# Microcontroller.net
KiCad netlist of a schematic drawn in Altium Designer
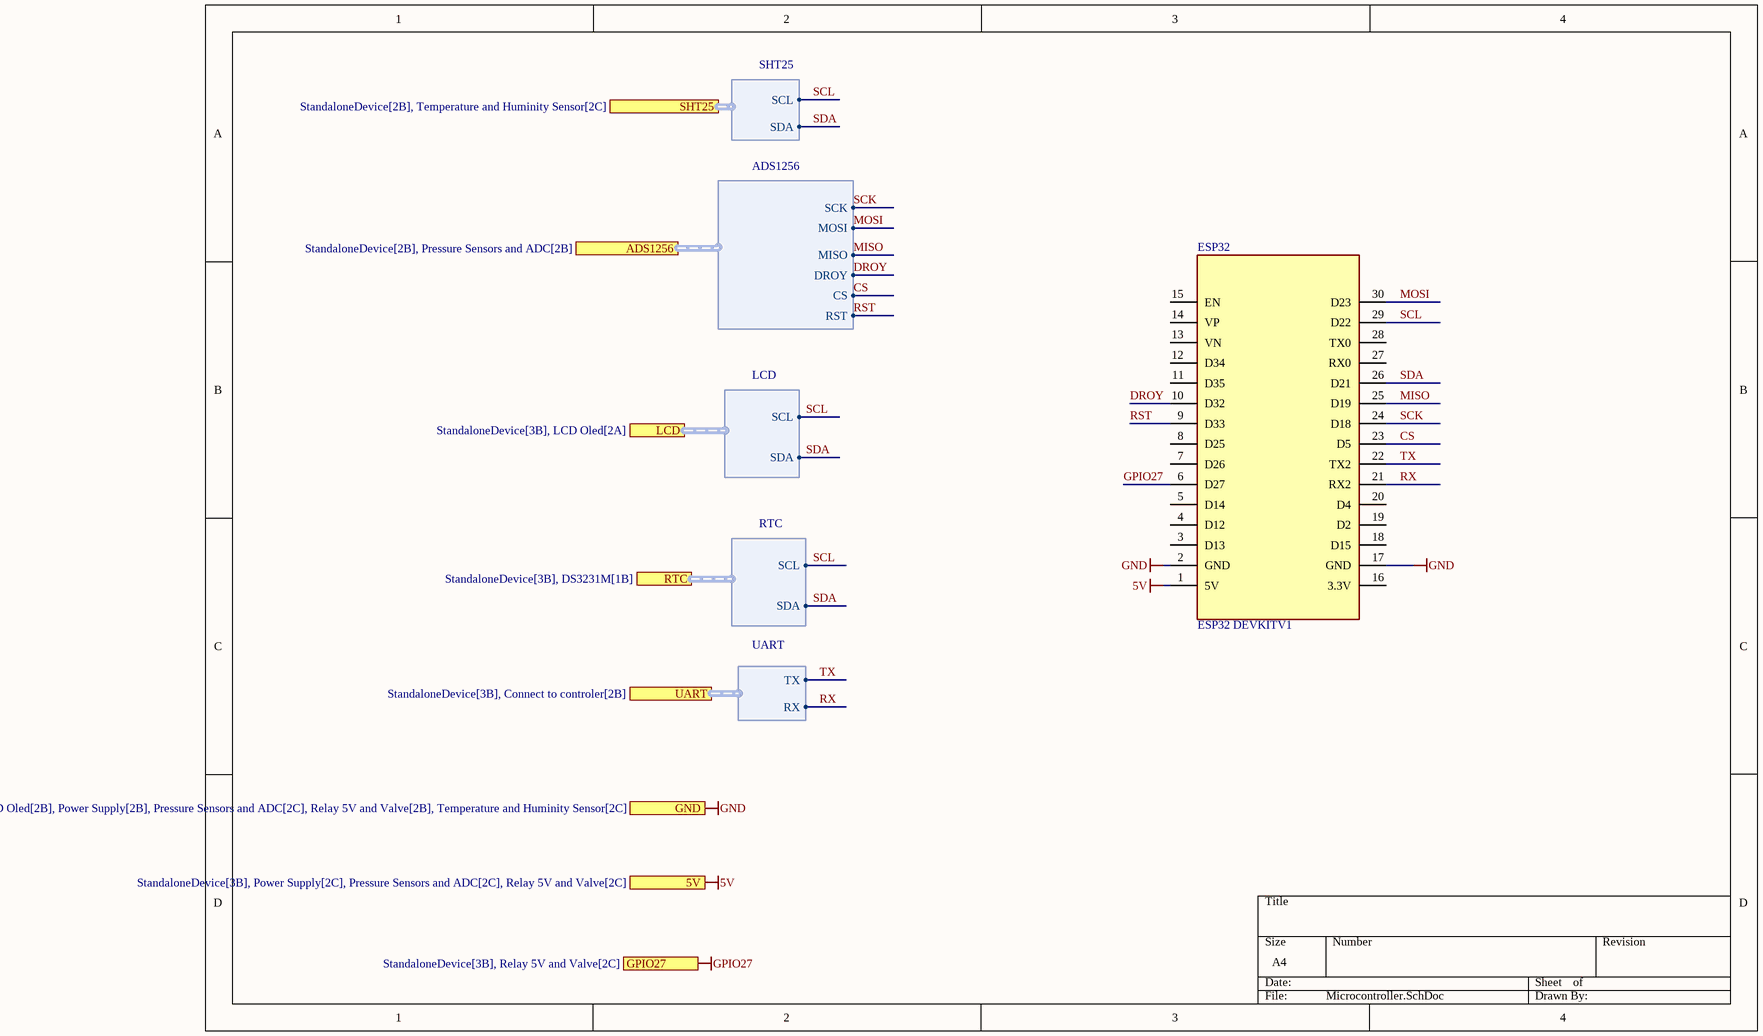
[diagram p0: Microcontroller.SchDoc]

(export (version "E")
  (design (tool "Eeschema 10.0.6"))
  (components
    (comp (ref "ESP32")
      (value "ESP32 DEVKITV1")
      (footprint "ESP32 DEVKITV1")
      (fields (field (name "MF") "Espressif Systems") (field (name "MP") "ESP32 NODEMCU"))
      (libsource (lib "KHOEMACH_SCHLIB") (part "ESP32 DEVKITV1"))
    )
  )
  (nets
    (net (code "7") (name "/CS") (class "Default")
      (node (ref "ESP32") (pin "23") (pinfunction "D5_23") (pintype "power_in"))
    )
    (net (code "8") (name "/DROY") (class "Default")
      (node (ref "ESP32") (pin "10") (pinfunction "D32_10") (pintype "power_in"))
    )
    (net (code "9") (name "/MISO") (class "Default")
      (node (ref "ESP32") (pin "25") (pinfunction "D19_25") (pintype "power_in"))
    )
    (net (code "10") (name "/MOSI") (class "Default")
      (node (ref "ESP32") (pin "30") (pinfunction "D23_30") (pintype "power_in"))
    )
    (net (code "11") (name "/RST") (class "Default")
      (node (ref "ESP32") (pin "9") (pinfunction "D33_9") (pintype "power_in"))
    )
    (net (code "12") (name "/RX") (class "Default")
      (node (ref "ESP32") (pin "21") (pinfunction "RX2_21") (pintype "power_in"))
    )
    (net (code "13") (name "/SCK") (class "Default")
      (node (ref "ESP32") (pin "24") (pinfunction "D18_24") (pintype "power_in"))
    )
    (net (code "14") (name "/SCL") (class "Default")
      (node (ref "ESP32") (pin "29") (pinfunction "D22_29") (pintype "power_in"))
    )
    (net (code "15") (name "/SDA") (class "Default")
      (node (ref "ESP32") (pin "26") (pinfunction "D21_26") (pintype "power_in"))
    )
    (net (code "16") (name "/TX") (class "Default")
      (node (ref "ESP32") (pin "22") (pinfunction "TX2_22") (pintype "power_in"))
    )
    (net (code "22") (name "5V") (class "Default")
      (node (ref "ESP32") (pin "1") (pinfunction "5V_1") (pintype "power_in"))
    )
    (net (code "23") (name "GND") (class "Default")
      (node (ref "ESP32") (pin "17") (pinfunction "GND_17") (pintype "power_in"))
      (node (ref "ESP32") (pin "2") (pinfunction "GND_2") (pintype "power_in"))
    )
    (net (code "24") (name "GPIO27") (class "Default")
      (node (ref "ESP32") (pin "6") (pinfunction "D27_6") (pintype "power_in"))
    )
    (net (code "25") (name "unconnected-(ESP32-3.3V-Pad16)") (class "Default")
      (node (ref "ESP32") (pin "16") (pinfunction "3.3V_16") (pintype "power_in"))
    )
    (net (code "26") (name "unconnected-(ESP32-D2-Pad19)") (class "Default")
      (node (ref "ESP32") (pin "19") (pinfunction "D2_19") (pintype "power_in"))
    )
    (net (code "27") (name "unconnected-(ESP32-D4-Pad20)") (class "Default")
      (node (ref "ESP32") (pin "20") (pinfunction "D4_20") (pintype "power_in"))
    )
    (net (code "28") (name "unconnected-(ESP32-D12-Pad4)") (class "Default")
      (node (ref "ESP32") (pin "4") (pinfunction "D12_4") (pintype "power_in"))
    )
    (net (code "29") (name "unconnected-(ESP32-D13-Pad3)") (class "Default")
      (node (ref "ESP32") (pin "3") (pinfunction "D13_3") (pintype "power_in"))
    )
    (net (code "30") (name "unconnected-(ESP32-D14-Pad5)") (class "Default")
      (node (ref "ESP32") (pin "5") (pinfunction "D14_5") (pintype "power_in"))
    )
    (net (code "31") (name "unconnected-(ESP32-D15-Pad18)") (class "Default")
      (node (ref "ESP32") (pin "18") (pinfunction "D15_18") (pintype "power_in"))
    )
    (net (code "32") (name "unconnected-(ESP32-D25-Pad8)") (class "Default")
      (node (ref "ESP32") (pin "8") (pinfunction "D25_8") (pintype "power_in"))
    )
    (net (code "33") (name "unconnected-(ESP32-D26-Pad7)") (class "Default")
      (node (ref "ESP32") (pin "7") (pinfunction "D26_7") (pintype "power_in"))
    )
    (net (code "34") (name "unconnected-(ESP32-D34-Pad12)") (class "Default")
      (node (ref "ESP32") (pin "12") (pinfunction "D34_12") (pintype "power_in"))
    )
    (net (code "35") (name "unconnected-(ESP32-D35-Pad11)") (class "Default")
      (node (ref "ESP32") (pin "11") (pinfunction "D35_11") (pintype "power_in"))
    )
    (net (code "36") (name "unconnected-(ESP32-EN-Pad15)") (class "Default")
      (node (ref "ESP32") (pin "15") (pinfunction "EN_15") (pintype "power_in"))
    )
    (net (code "37") (name "unconnected-(ESP32-RX0-Pad27)") (class "Default")
      (node (ref "ESP32") (pin "27") (pinfunction "RX0_27") (pintype "power_in"))
    )
    (net (code "38") (name "unconnected-(ESP32-TX0-Pad28)") (class "Default")
      (node (ref "ESP32") (pin "28") (pinfunction "TX0_28") (pintype "power_in"))
    )
    (net (code "39") (name "unconnected-(ESP32-VN-Pad13)") (class "Default")
      (node (ref "ESP32") (pin "13") (pinfunction "VN_13") (pintype "power_in"))
    )
    (net (code "40") (name "unconnected-(ESP32-VP-Pad14)") (class "Default")
      (node (ref "ESP32") (pin "14") (pinfunction "VP_14") (pintype "power_in"))
    )
  )
)
